# IO.net
KiCad netlist of a schematic drawn in Altium Designer
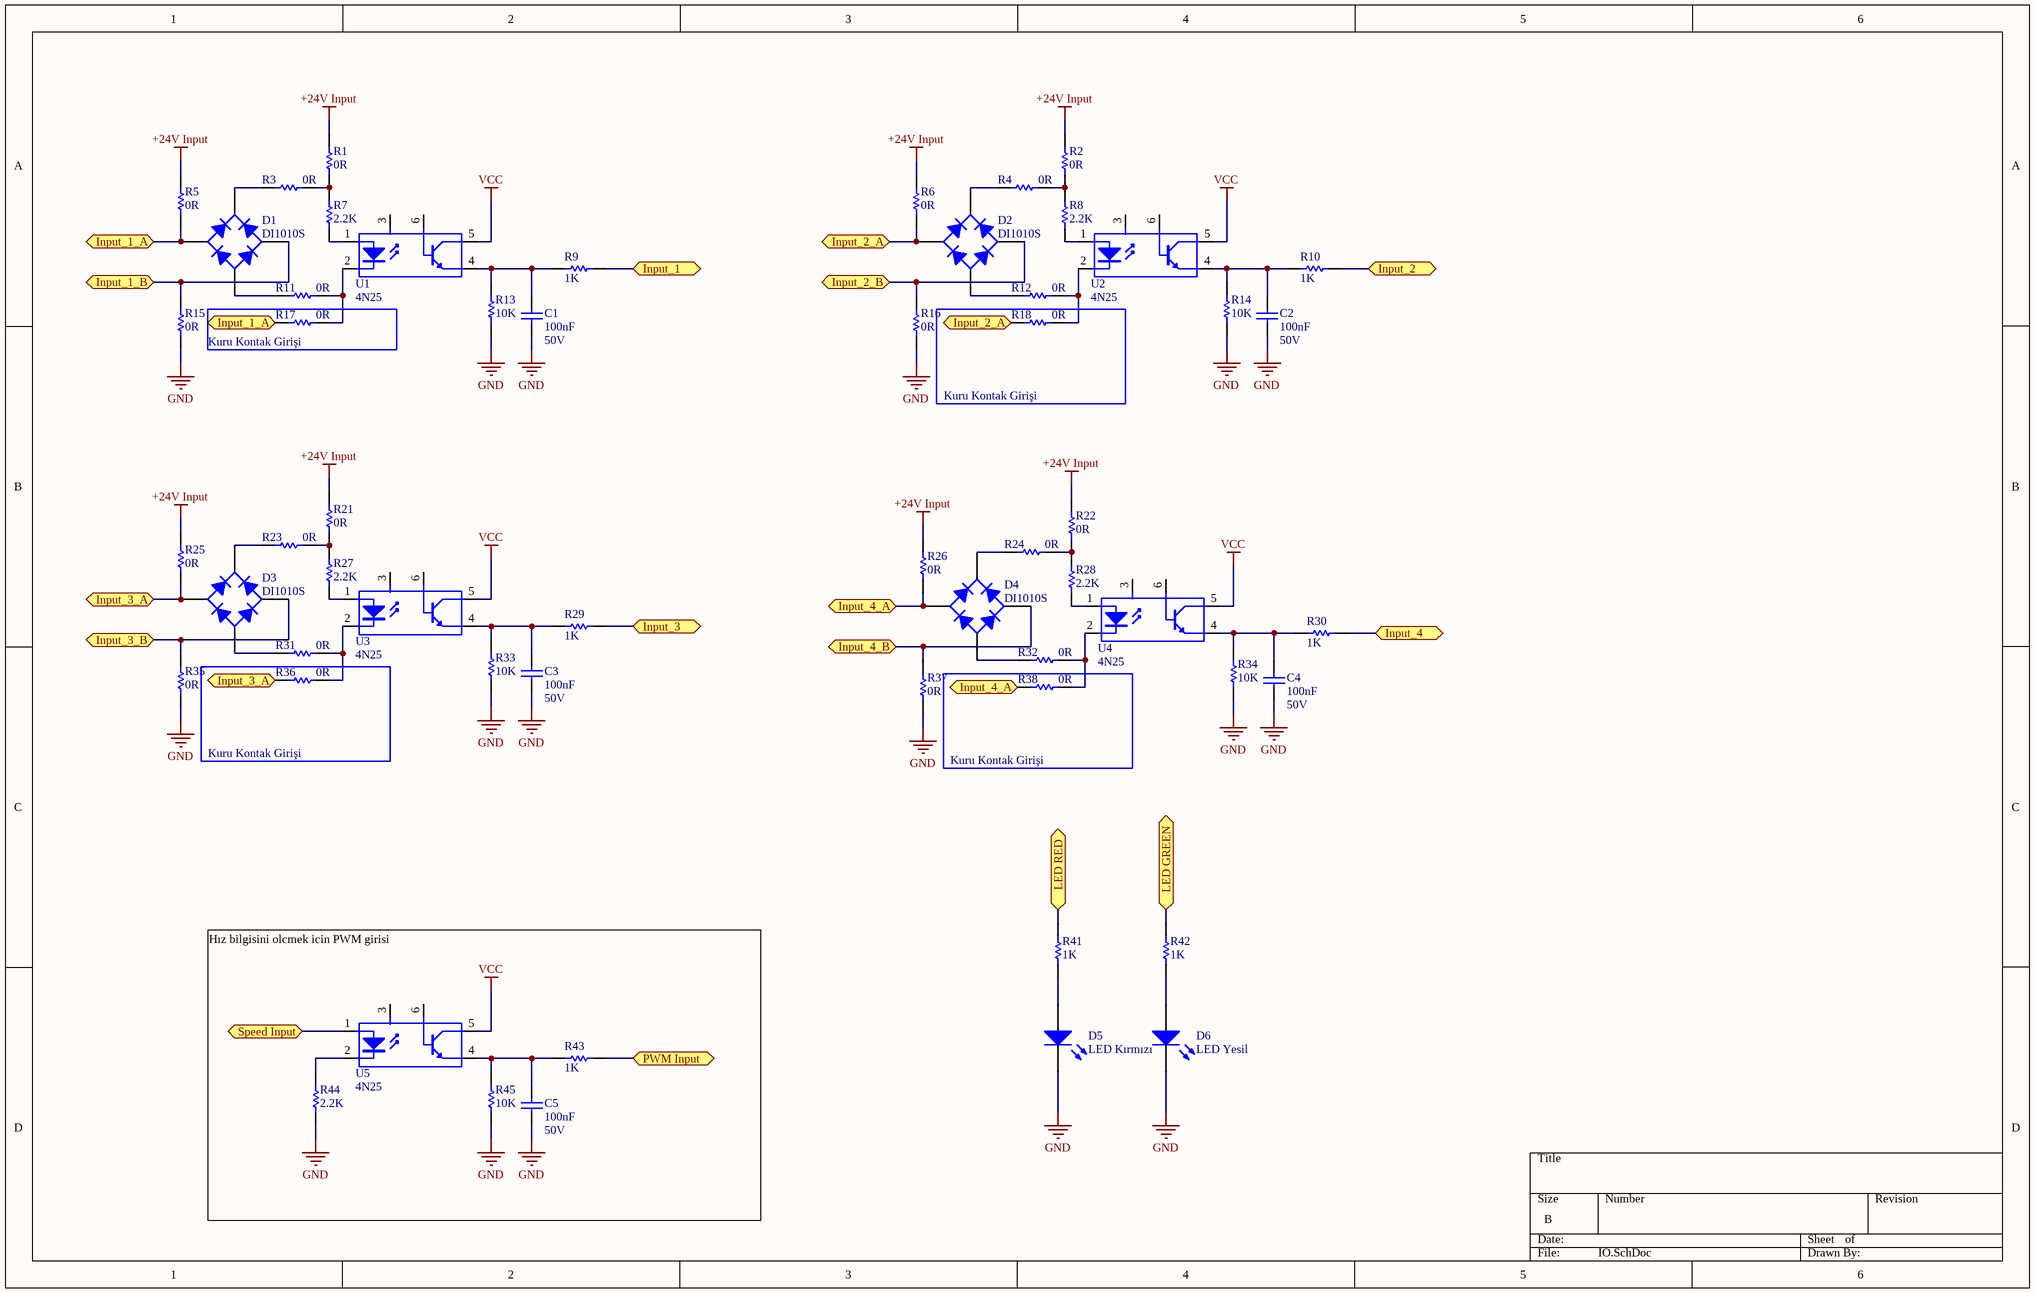
[diagram p0: IO.SchDoc]

(export (version "E")
  (design (tool "Eeschema 10.0.6"))
  (components
    (comp (ref "C1")
      (value "100nF")
      (footprint "3-0603_L")
      (description "Capacitor")
      (fields
        (field (name "VOLTAGE") "50V")
        (field (name "Comment") "Cap")
        (field (name "PUBLISHER") "Altium Limited")
      )
      (libsource (lib "Erdem_05112012") (part "Cap"))
    )
    (comp (ref "C2")
      (value "100nF")
      (footprint "3-0603_L")
      (description "Capacitor")
      (fields
        (field (name "VOLTAGE") "50V")
        (field (name "Comment") "Cap")
        (field (name "PUBLISHER") "Altium Limited")
      )
      (libsource (lib "Erdem_05112012") (part "Cap"))
    )
    (comp (ref "C3")
      (value "100nF")
      (footprint "3-0603_L")
      (description "Capacitor")
      (fields
        (field (name "VOLTAGE") "50V")
        (field (name "Comment") "Cap")
        (field (name "PUBLISHER") "Altium Limited")
      )
      (libsource (lib "Erdem_05112012") (part "Cap"))
    )
    (comp (ref "C4")
      (value "100nF")
      (footprint "3-0603_L")
      (description "Capacitor")
      (fields
        (field (name "VOLTAGE") "50V")
        (field (name "Comment") "Cap")
        (field (name "PUBLISHER") "Altium Limited")
      )
      (libsource (lib "Erdem_05112012") (part "Cap"))
    )
    (comp (ref "C5")
      (value "100nF")
      (footprint "3-0603_L")
      (description "Capacitor")
      (fields
        (field (name "VOLTAGE") "50V")
        (field (name "Comment") "Cap")
        (field (name "PUBLISHER") "Altium Limited")
      )
      (libsource (lib "Erdem_05112012") (part "Cap"))
    )
    (comp (ref "D1")
      (value "DI1010S")
      (footprint "DF-S")
      (description "Full Wave Diode Bridge")
      (fields (field (name "PUBLISHER") "Altium Limited"))
      (libsource (lib "Erdem_05112012") (part "DI1010S"))
    )
    (comp (ref "D2")
      (value "DI1010S")
      (footprint "DF-S")
      (description "Full Wave Diode Bridge")
      (fields (field (name "PUBLISHER") "Altium Limited"))
      (libsource (lib "Erdem_05112012") (part "DI1010S"))
    )
    (comp (ref "D3")
      (value "DI1010S")
      (footprint "DF-S")
      (description "Full Wave Diode Bridge")
      (fields (field (name "PUBLISHER") "Altium Limited"))
      (libsource (lib "Erdem_05112012") (part "DI1010S"))
    )
    (comp (ref "D4")
      (value "DI1010S")
      (footprint "DF-S")
      (description "Full Wave Diode Bridge")
      (fields (field (name "PUBLISHER") "Altium Limited"))
      (libsource (lib "Erdem_05112012") (part "DI1010S"))
    )
    (comp (ref "D5")
      (value "LED Kırmızı")
      (footprint "6-0805 - LED")
      (description "Typical INFRARED GaAs LED")
      (fields (field (name "PUBLISHER") "Altium Limited"))
      (libsource (lib "Erdem_05112012") (part "LED"))
    )
    (comp (ref "D6")
      (value "LED Yesil")
      (footprint "6-0805 - LED")
      (description "Typical INFRARED GaAs LED")
      (fields (field (name "PUBLISHER") "Altium Limited"))
      (libsource (lib "Erdem_05112012") (part "LED"))
    )
    (comp (ref "R1")
      (value "0R")
      (footprint "6-0805_M")
      (description "Resistor")
      (fields (field (name "Comment") "Res1") (field (name "PUBLISHER") "Altium Limited"))
      (libsource (lib "Erdem_05112012") (part "Res1"))
    )
    (comp (ref "R2")
      (value "0R")
      (footprint "6-0805_M")
      (description "Resistor")
      (fields (field (name "Comment") "Res1") (field (name "PUBLISHER") "Altium Limited"))
      (libsource (lib "Erdem_05112012") (part "Res1"))
    )
    (comp (ref "R3")
      (value "0R")
      (footprint "6-0805_M")
      (description "Resistor")
      (fields (field (name "Comment") "Res1") (field (name "PUBLISHER") "Altium Limited"))
      (libsource (lib "Erdem_05112012") (part "Res1"))
    )
    (comp (ref "R4")
      (value "0R")
      (footprint "6-0805_M")
      (description "Resistor")
      (fields (field (name "Comment") "Res1") (field (name "PUBLISHER") "Altium Limited"))
      (libsource (lib "Erdem_05112012") (part "Res1"))
    )
    (comp (ref "R5")
      (value "0R")
      (footprint "6-0805_M")
      (description "Resistor")
      (fields (field (name "Comment") "Res1") (field (name "PUBLISHER") "Altium Limited"))
      (libsource (lib "Erdem_05112012") (part "Res1"))
    )
    (comp (ref "R6")
      (value "0R")
      (footprint "6-0805_M")
      (description "Resistor")
      (fields (field (name "Comment") "Res1") (field (name "PUBLISHER") "Altium Limited"))
      (libsource (lib "Erdem_05112012") (part "Res1"))
    )
    (comp (ref "R7")
      (value "2.2K")
      (footprint "6-0805_M")
      (description "Resistor")
      (fields (field (name "Comment") "Res1") (field (name "PUBLISHER") "Altium Limited"))
      (libsource (lib "Erdem_05112012") (part "Res1"))
    )
    (comp (ref "R8")
      (value "2.2K")
      (footprint "6-0805_M")
      (description "Resistor")
      (fields (field (name "Comment") "Res1") (field (name "PUBLISHER") "Altium Limited"))
      (libsource (lib "Erdem_05112012") (part "Res1"))
    )
    (comp (ref "R9")
      (value "1K")
      (footprint "3-0603_L")
      (description "Resistor")
      (fields (field (name "Comment") "Res1") (field (name "PUBLISHER") "Altium Limited"))
      (libsource (lib "Erdem_05112012") (part "Res1"))
    )
    (comp (ref "R10")
      (value "1K")
      (footprint "3-0603_L")
      (description "Resistor")
      (fields (field (name "Comment") "Res1") (field (name "PUBLISHER") "Altium Limited"))
      (libsource (lib "Erdem_05112012") (part "Res1"))
    )
    (comp (ref "R11")
      (value "0R")
      (footprint "6-0805_M")
      (description "Resistor")
      (fields (field (name "Comment") "Res1") (field (name "PUBLISHER") "Altium Limited"))
      (libsource (lib "Erdem_05112012") (part "Res1"))
    )
    (comp (ref "R12")
      (value "0R")
      (footprint "6-0805_M")
      (description "Resistor")
      (fields (field (name "Comment") "Res1") (field (name "PUBLISHER") "Altium Limited"))
      (libsource (lib "Erdem_05112012") (part "Res1"))
    )
    (comp (ref "R13")
      (value "10K")
      (footprint "3-0603_L")
      (description "Resistor")
      (fields (field (name "Comment") "Res1") (field (name "PUBLISHER") "Altium Limited"))
      (libsource (lib "Erdem_05112012") (part "Res1"))
    )
    (comp (ref "R14")
      (value "10K")
      (footprint "3-0603_L")
      (description "Resistor")
      (fields (field (name "Comment") "Res1") (field (name "PUBLISHER") "Altium Limited"))
      (libsource (lib "Erdem_05112012") (part "Res1"))
    )
    (comp (ref "R15")
      (value "0R")
      (footprint "6-0805_M")
      (description "Resistor")
      (fields (field (name "Comment") "Res1") (field (name "PUBLISHER") "Altium Limited"))
      (libsource (lib "Erdem_05112012") (part "Res1"))
    )
    (comp (ref "R16")
      (value "0R")
      (footprint "6-0805_M")
      (description "Resistor")
      (fields (field (name "Comment") "Res1") (field (name "PUBLISHER") "Altium Limited"))
      (libsource (lib "Erdem_05112012") (part "Res1"))
    )
    (comp (ref "R17")
      (value "0R")
      (footprint "6-0805_M")
      (description "Resistor")
      (fields (field (name "Comment") "Res1") (field (name "PUBLISHER") "Altium Limited"))
      (libsource (lib "Erdem_05112012") (part "Res1"))
    )
    (comp (ref "R18")
      (value "0R")
      (footprint "6-0805_M")
      (description "Resistor")
      (fields (field (name "Comment") "Res1") (field (name "PUBLISHER") "Altium Limited"))
      (libsource (lib "Erdem_05112012") (part "Res1"))
    )
    (comp (ref "R21")
      (value "0R")
      (footprint "6-0805_M")
      (description "Resistor")
      (fields (field (name "Comment") "Res1") (field (name "PUBLISHER") "Altium Limited"))
      (libsource (lib "Erdem_05112012") (part "Res1"))
    )
    (comp (ref "R22")
      (value "0R")
      (footprint "6-0805_M")
      (description "Resistor")
      (fields (field (name "Comment") "Res1") (field (name "PUBLISHER") "Altium Limited"))
      (libsource (lib "Erdem_05112012") (part "Res1"))
    )
    (comp (ref "R23")
      (value "0R")
      (footprint "6-0805_M")
      (description "Resistor")
      (fields (field (name "Comment") "Res1") (field (name "PUBLISHER") "Altium Limited"))
      (libsource (lib "Erdem_05112012") (part "Res1"))
    )
    (comp (ref "R24")
      (value "0R")
      (footprint "6-0805_M")
      (description "Resistor")
      (fields (field (name "Comment") "Res1") (field (name "PUBLISHER") "Altium Limited"))
      (libsource (lib "Erdem_05112012") (part "Res1"))
    )
    (comp (ref "R25")
      (value "0R")
      (footprint "6-0805_M")
      (description "Resistor")
      (fields (field (name "Comment") "Res1") (field (name "PUBLISHER") "Altium Limited"))
      (libsource (lib "Erdem_05112012") (part "Res1"))
    )
    (comp (ref "R26")
      (value "0R")
      (footprint "6-0805_M")
      (description "Resistor")
      (fields (field (name "Comment") "Res1") (field (name "PUBLISHER") "Altium Limited"))
      (libsource (lib "Erdem_05112012") (part "Res1"))
    )
    (comp (ref "R27")
      (value "2.2K")
      (footprint "6-0805_M")
      (description "Resistor")
      (fields (field (name "Comment") "Res1") (field (name "PUBLISHER") "Altium Limited"))
      (libsource (lib "Erdem_05112012") (part "Res1"))
    )
    (comp (ref "R28")
      (value "2.2K")
      (footprint "6-0805_M")
      (description "Resistor")
      (fields (field (name "Comment") "Res1") (field (name "PUBLISHER") "Altium Limited"))
      (libsource (lib "Erdem_05112012") (part "Res1"))
    )
    (comp (ref "R29")
      (value "1K")
      (footprint "3-0603_L")
      (description "Resistor")
      (fields (field (name "Comment") "Res1") (field (name "PUBLISHER") "Altium Limited"))
      (libsource (lib "Erdem_05112012") (part "Res1"))
    )
    (comp (ref "R30")
      (value "1K")
      (footprint "3-0603_L")
      (description "Resistor")
      (fields (field (name "Comment") "Res1") (field (name "PUBLISHER") "Altium Limited"))
      (libsource (lib "Erdem_05112012") (part "Res1"))
    )
    (comp (ref "R31")
      (value "0R")
      (footprint "6-0805_M")
      (description "Resistor")
      (fields (field (name "Comment") "Res1") (field (name "PUBLISHER") "Altium Limited"))
      (libsource (lib "Erdem_05112012") (part "Res1"))
    )
    (comp (ref "R32")
      (value "0R")
      (footprint "6-0805_M")
      (description "Resistor")
      (fields (field (name "Comment") "Res1") (field (name "PUBLISHER") "Altium Limited"))
      (libsource (lib "Erdem_05112012") (part "Res1"))
    )
    (comp (ref "R33")
      (value "10K")
      (footprint "3-0603_L")
      (description "Resistor")
      (fields (field (name "Comment") "Res1") (field (name "PUBLISHER") "Altium Limited"))
      (libsource (lib "Erdem_05112012") (part "Res1"))
    )
    (comp (ref "R34")
      (value "10K")
      (footprint "3-0603_L")
      (description "Resistor")
      (fields (field (name "Comment") "Res1") (field (name "PUBLISHER") "Altium Limited"))
      (libsource (lib "Erdem_05112012") (part "Res1"))
    )
    (comp (ref "R35")
      (value "0R")
      (footprint "6-0805_M")
      (description "Resistor")
      (fields (field (name "Comment") "Res1") (field (name "PUBLISHER") "Altium Limited"))
      (libsource (lib "Erdem_05112012") (part "Res1"))
    )
    (comp (ref "R36")
      (value "0R")
      (footprint "6-0805_M")
      (description "Resistor")
      (fields (field (name "Comment") "Res1") (field (name "PUBLISHER") "Altium Limited"))
      (libsource (lib "Erdem_05112012") (part "Res1"))
    )
    (comp (ref "R37")
      (value "0R")
      (footprint "6-0805_M")
      (description "Resistor")
      (fields (field (name "Comment") "Res1") (field (name "PUBLISHER") "Altium Limited"))
      (libsource (lib "Erdem_05112012") (part "Res1"))
    )
    (comp (ref "R38")
      (value "0R")
      (footprint "6-0805_M")
      (description "Resistor")
      (fields (field (name "Comment") "Res1") (field (name "PUBLISHER") "Altium Limited"))
      (libsource (lib "Erdem_05112012") (part "Res1"))
    )
    (comp (ref "R41")
      (value "1K")
      (footprint "3-0603_L")
      (description "Resistor")
      (fields (field (name "Comment") "Res1") (field (name "PUBLISHER") "Altium Limited"))
      (libsource (lib "Erdem_05112012") (part "Res1"))
    )
    (comp (ref "R42")
      (value "1K")
      (footprint "3-0603_L")
      (description "Resistor")
      (fields (field (name "Comment") "Res1") (field (name "PUBLISHER") "Altium Limited"))
      (libsource (lib "Erdem_05112012") (part "Res1"))
    )
    (comp (ref "R43")
      (value "1K")
      (footprint "3-0603_L")
      (description "Resistor")
      (fields (field (name "Comment") "Res1") (field (name "PUBLISHER") "Altium Limited"))
      (libsource (lib "Erdem_05112012") (part "Res1"))
    )
    (comp (ref "R44")
      (value "2.2K")
      (footprint "6-0805_M")
      (description "Resistor")
      (fields (field (name "Comment") "Res1") (field (name "PUBLISHER") "Altium Limited"))
      (libsource (lib "Erdem_05112012") (part "Res1"))
    )
    (comp (ref "R45")
      (value "10K")
      (footprint "3-0603_L")
      (description "Resistor")
      (fields (field (name "Comment") "Res1") (field (name "PUBLISHER") "Altium Limited"))
      (libsource (lib "Erdem_05112012") (part "Res1"))
    )
    (comp (ref "U1")
      (value "4N25")
      (footprint "DIP-6")
      (fields (field (name "PUBLISHER") "Altium Limited"))
      (libsource (lib "Erdem_05112012") (part "4N25"))
    )
    (comp (ref "U2")
      (value "4N25")
      (footprint "DIP-6")
      (fields (field (name "PUBLISHER") "Altium Limited"))
      (libsource (lib "Erdem_05112012") (part "4N25"))
    )
    (comp (ref "U3")
      (value "4N25")
      (footprint "DIP-6")
      (fields (field (name "PUBLISHER") "Altium Limited"))
      (libsource (lib "Erdem_05112012") (part "4N25"))
    )
    (comp (ref "U4")
      (value "4N25")
      (footprint "DIP-6")
      (fields (field (name "PUBLISHER") "Altium Limited"))
      (libsource (lib "Erdem_05112012") (part "4N25"))
    )
    (comp (ref "U5")
      (value "4N25")
      (footprint "DIP-6")
      (fields (field (name "PUBLISHER") "Altium Limited"))
      (libsource (lib "Erdem_05112012") (part "4N25"))
    )
  )
  (nets
    (net (code "1") (name "+24V Input") (class "Default")
      (node (ref "R1") (pin "2") (pinfunction "2_2") (pintype "passive"))
      (node (ref "R2") (pin "2") (pinfunction "2_2") (pintype "passive"))
      (node (ref "R21") (pin "2") (pinfunction "2_2") (pintype "passive"))
      (node (ref "R22") (pin "2") (pinfunction "2_2") (pintype "passive"))
      (node (ref "R25") (pin "2") (pinfunction "2_2") (pintype "passive"))
      (node (ref "R26") (pin "2") (pinfunction "2_2") (pintype "passive"))
      (node (ref "R5") (pin "2") (pinfunction "2_2") (pintype "passive"))
      (node (ref "R6") (pin "2") (pinfunction "2_2") (pintype "passive"))
    )
    (net (code "2") (name "/Input_1") (class "Default")
      (node (ref "R9") (pin "2") (pinfunction "2_2") (pintype "passive"))
    )
    (net (code "3") (name "/Input_1_A") (class "Default")
      (node (ref "D1") (pin "2") (pinfunction "C_2") (pintype "passive"))
      (node (ref "R17") (pin "2") (pinfunction "2_2") (pintype "passive"))
      (node (ref "R5") (pin "1") (pinfunction "1_1") (pintype "passive"))
    )
    (net (code "4") (name "/Input_1_B") (class "Default")
      (node (ref "D1") (pin "4") (pinfunction "C_4") (pintype "passive"))
      (node (ref "R15") (pin "2") (pinfunction "2_2") (pintype "passive"))
    )
    (net (code "5") (name "/Input_2") (class "Default")
      (node (ref "R10") (pin "2") (pinfunction "2_2") (pintype "passive"))
    )
    (net (code "6") (name "/Input_2_A") (class "Default")
      (node (ref "D2") (pin "2") (pinfunction "C_2") (pintype "passive"))
      (node (ref "R18") (pin "2") (pinfunction "2_2") (pintype "passive"))
      (node (ref "R6") (pin "1") (pinfunction "1_1") (pintype "passive"))
    )
    (net (code "7") (name "/Input_2_B") (class "Default")
      (node (ref "D2") (pin "4") (pinfunction "C_4") (pintype "passive"))
      (node (ref "R16") (pin "2") (pinfunction "2_2") (pintype "passive"))
    )
    (net (code "8") (name "/Input_3") (class "Default")
      (node (ref "R29") (pin "2") (pinfunction "2_2") (pintype "passive"))
    )
    (net (code "9") (name "/Input_3_A") (class "Default")
      (node (ref "D3") (pin "2") (pinfunction "C_2") (pintype "passive"))
      (node (ref "R25") (pin "1") (pinfunction "1_1") (pintype "passive"))
      (node (ref "R36") (pin "2") (pinfunction "2_2") (pintype "passive"))
    )
    (net (code "10") (name "/Input_3_B") (class "Default")
      (node (ref "D3") (pin "4") (pinfunction "C_4") (pintype "passive"))
      (node (ref "R35") (pin "2") (pinfunction "2_2") (pintype "passive"))
    )
    (net (code "11") (name "/Input_4") (class "Default")
      (node (ref "R30") (pin "2") (pinfunction "2_2") (pintype "passive"))
    )
    (net (code "12") (name "/Input_4_A") (class "Default")
      (node (ref "D4") (pin "2") (pinfunction "C_2") (pintype "passive"))
      (node (ref "R26") (pin "1") (pinfunction "1_1") (pintype "passive"))
      (node (ref "R38") (pin "2") (pinfunction "2_2") (pintype "passive"))
    )
    (net (code "13") (name "/Input_4_B") (class "Default")
      (node (ref "D4") (pin "4") (pinfunction "C_4") (pintype "passive"))
      (node (ref "R37") (pin "2") (pinfunction "2_2") (pintype "passive"))
    )
    (net (code "14") (name "/LED GREEN") (class "Default")
      (node (ref "R42") (pin "2") (pinfunction "2_2") (pintype "passive"))
    )
    (net (code "15") (name "/LED RED") (class "Default")
      (node (ref "R41") (pin "2") (pinfunction "2_2") (pintype "passive"))
    )
    (net (code "16") (name "/PWM Input") (class "Default")
      (node (ref "R43") (pin "2") (pinfunction "2_2") (pintype "passive"))
    )
    (net (code "17") (name "/Speed Input") (class "Default")
      (node (ref "U5") (pin "1") (pinfunction "A_1") (pintype "passive"))
    )
    (net (code "18") (name "GND") (class "Default")
      (node (ref "C1") (pin "2") (pinfunction "2_2") (pintype "passive"))
      (node (ref "C2") (pin "2") (pinfunction "2_2") (pintype "passive"))
      (node (ref "C3") (pin "2") (pinfunction "2_2") (pintype "passive"))
      (node (ref "C4") (pin "2") (pinfunction "2_2") (pintype "passive"))
      (node (ref "C5") (pin "2") (pinfunction "2_2") (pintype "passive"))
      (node (ref "D5") (pin "2") (pinfunction "K_2") (pintype "passive"))
      (node (ref "D6") (pin "2") (pinfunction "K_2") (pintype "passive"))
      (node (ref "R13") (pin "1") (pinfunction "1_1") (pintype "passive"))
      (node (ref "R14") (pin "1") (pinfunction "1_1") (pintype "passive"))
      (node (ref "R15") (pin "1") (pinfunction "1_1") (pintype "passive"))
      (node (ref "R16") (pin "1") (pinfunction "1_1") (pintype "passive"))
      (node (ref "R33") (pin "1") (pinfunction "1_1") (pintype "passive"))
      (node (ref "R34") (pin "1") (pinfunction "1_1") (pintype "passive"))
      (node (ref "R35") (pin "1") (pinfunction "1_1") (pintype "passive"))
      (node (ref "R37") (pin "1") (pinfunction "1_1") (pintype "passive"))
      (node (ref "R44") (pin "1") (pinfunction "1_1") (pintype "passive"))
      (node (ref "R45") (pin "1") (pinfunction "1_1") (pintype "passive"))
    )
    (net (code "19") (name "Net-(D1-A)") (class "Default")
      (node (ref "D1") (pin "1") (pinfunction "A_1") (pintype "passive"))
      (node (ref "R11") (pin "2") (pinfunction "2_2") (pintype "passive"))
    )
    (net (code "20") (name "Net-(D1-K)") (class "Default")
      (node (ref "D1") (pin "3") (pinfunction "K_3") (pintype "passive"))
      (node (ref "R3") (pin "2") (pinfunction "2_2") (pintype "passive"))
    )
    (net (code "21") (name "Net-(D2-A)") (class "Default")
      (node (ref "D2") (pin "1") (pinfunction "A_1") (pintype "passive"))
      (node (ref "R12") (pin "2") (pinfunction "2_2") (pintype "passive"))
    )
    (net (code "22") (name "Net-(D2-K)") (class "Default")
      (node (ref "D2") (pin "3") (pinfunction "K_3") (pintype "passive"))
      (node (ref "R4") (pin "2") (pinfunction "2_2") (pintype "passive"))
    )
    (net (code "23") (name "Net-(D3-A)") (class "Default")
      (node (ref "D3") (pin "1") (pinfunction "A_1") (pintype "passive"))
      (node (ref "R31") (pin "2") (pinfunction "2_2") (pintype "passive"))
    )
    (net (code "24") (name "Net-(D3-K)") (class "Default")
      (node (ref "D3") (pin "3") (pinfunction "K_3") (pintype "passive"))
      (node (ref "R23") (pin "2") (pinfunction "2_2") (pintype "passive"))
    )
    (net (code "25") (name "Net-(D4-A)") (class "Default")
      (node (ref "D4") (pin "1") (pinfunction "A_1") (pintype "passive"))
      (node (ref "R32") (pin "2") (pinfunction "2_2") (pintype "passive"))
    )
    (net (code "26") (name "Net-(D4-K)") (class "Default")
      (node (ref "D4") (pin "3") (pinfunction "K_3") (pintype "passive"))
      (node (ref "R24") (pin "2") (pinfunction "2_2") (pintype "passive"))
    )
    (net (code "27") (name "Net-(D5-A)") (class "Default")
      (node (ref "D5") (pin "1") (pinfunction "A_1") (pintype "passive"))
      (node (ref "R41") (pin "1") (pinfunction "1_1") (pintype "passive"))
    )
    (net (code "28") (name "Net-(D6-A)") (class "Default")
      (node (ref "D6") (pin "1") (pinfunction "A_1") (pintype "passive"))
      (node (ref "R42") (pin "1") (pinfunction "1_1") (pintype "passive"))
    )
    (net (code "29") (name "Net-(R1-Pad1)") (class "Default")
      (node (ref "R1") (pin "1") (pinfunction "1_1") (pintype "passive"))
      (node (ref "R3") (pin "1") (pinfunction "1_1") (pintype "passive"))
      (node (ref "R7") (pin "1") (pinfunction "1_1") (pintype "passive"))
    )
    (net (code "30") (name "Net-(R2-Pad1)") (class "Default")
      (node (ref "R2") (pin "1") (pinfunction "1_1") (pintype "passive"))
      (node (ref "R4") (pin "1") (pinfunction "1_1") (pintype "passive"))
      (node (ref "R8") (pin "1") (pinfunction "1_1") (pintype "passive"))
    )
    (net (code "31") (name "Net-(R21-Pad1)") (class "Default")
      (node (ref "R21") (pin "1") (pinfunction "1_1") (pintype "passive"))
      (node (ref "R23") (pin "1") (pinfunction "1_1") (pintype "passive"))
      (node (ref "R27") (pin "1") (pinfunction "1_1") (pintype "passive"))
    )
    (net (code "32") (name "Net-(R22-Pad1)") (class "Default")
      (node (ref "R22") (pin "1") (pinfunction "1_1") (pintype "passive"))
      (node (ref "R24") (pin "1") (pinfunction "1_1") (pintype "passive"))
      (node (ref "R28") (pin "1") (pinfunction "1_1") (pintype "passive"))
    )
    (net (code "33") (name "Net-(U1-A)") (class "Default")
      (node (ref "R7") (pin "2") (pinfunction "2_2") (pintype "passive"))
      (node (ref "U1") (pin "1") (pinfunction "A_1") (pintype "passive"))
    )
    (net (code "34") (name "Net-(U1-E)") (class "Default")
      (node (ref "C1") (pin "1") (pinfunction "1_1") (pintype "passive"))
      (node (ref "R13") (pin "2") (pinfunction "2_2") (pintype "passive"))
      (node (ref "R9") (pin "1") (pinfunction "1_1") (pintype "passive"))
      (node (ref "U1") (pin "4") (pinfunction "E_4") (pintype "passive"))
    )
    (net (code "35") (name "Net-(U1-K)") (class "Default")
      (node (ref "R11") (pin "1") (pinfunction "1_1") (pintype "passive"))
      (node (ref "R17") (pin "1") (pinfunction "1_1") (pintype "passive"))
      (node (ref "U1") (pin "2") (pinfunction "K_2") (pintype "passive"))
    )
    (net (code "36") (name "Net-(U2-A)") (class "Default")
      (node (ref "R8") (pin "2") (pinfunction "2_2") (pintype "passive"))
      (node (ref "U2") (pin "1") (pinfunction "A_1") (pintype "passive"))
    )
    (net (code "37") (name "Net-(U2-E)") (class "Default")
      (node (ref "C2") (pin "1") (pinfunction "1_1") (pintype "passive"))
      (node (ref "R10") (pin "1") (pinfunction "1_1") (pintype "passive"))
      (node (ref "R14") (pin "2") (pinfunction "2_2") (pintype "passive"))
      (node (ref "U2") (pin "4") (pinfunction "E_4") (pintype "passive"))
    )
    (net (code "38") (name "Net-(U2-K)") (class "Default")
      (node (ref "R12") (pin "1") (pinfunction "1_1") (pintype "passive"))
      (node (ref "R18") (pin "1") (pinfunction "1_1") (pintype "passive"))
      (node (ref "U2") (pin "2") (pinfunction "K_2") (pintype "passive"))
    )
    (net (code "39") (name "Net-(U3-A)") (class "Default")
      (node (ref "R27") (pin "2") (pinfunction "2_2") (pintype "passive"))
      (node (ref "U3") (pin "1") (pinfunction "A_1") (pintype "passive"))
    )
    (net (code "40") (name "Net-(U3-E)") (class "Default")
      (node (ref "C3") (pin "1") (pinfunction "1_1") (pintype "passive"))
      (node (ref "R29") (pin "1") (pinfunction "1_1") (pintype "passive"))
      (node (ref "R33") (pin "2") (pinfunction "2_2") (pintype "passive"))
      (node (ref "U3") (pin "4") (pinfunction "E_4") (pintype "passive"))
    )
    (net (code "41") (name "Net-(U3-K)") (class "Default")
      (node (ref "R31") (pin "1") (pinfunction "1_1") (pintype "passive"))
      (node (ref "R36") (pin "1") (pinfunction "1_1") (pintype "passive"))
      (node (ref "U3") (pin "2") (pinfunction "K_2") (pintype "passive"))
    )
    (net (code "42") (name "Net-(U4-A)") (class "Default")
      (node (ref "R28") (pin "2") (pinfunction "2_2") (pintype "passive"))
      (node (ref "U4") (pin "1") (pinfunction "A_1") (pintype "passive"))
    )
    (net (code "43") (name "Net-(U4-E)") (class "Default")
      (node (ref "C4") (pin "1") (pinfunction "1_1") (pintype "passive"))
      (node (ref "R30") (pin "1") (pinfunction "1_1") (pintype "passive"))
      (node (ref "R34") (pin "2") (pinfunction "2_2") (pintype "passive"))
      (node (ref "U4") (pin "4") (pinfunction "E_4") (pintype "passive"))
    )
    (net (code "44") (name "Net-(U4-K)") (class "Default")
      (node (ref "R32") (pin "1") (pinfunction "1_1") (pintype "passive"))
      (node (ref "R38") (pin "1") (pinfunction "1_1") (pintype "passive"))
      (node (ref "U4") (pin "2") (pinfunction "K_2") (pintype "passive"))
    )
    (net (code "45") (name "Net-(U5-E)") (class "Default")
      (node (ref "C5") (pin "1") (pinfunction "1_1") (pintype "passive"))
      (node (ref "R43") (pin "1") (pinfunction "1_1") (pintype "passive"))
      (node (ref "R45") (pin "2") (pinfunction "2_2") (pintype "passive"))
      (node (ref "U5") (pin "4") (pinfunction "E_4") (pintype "passive"))
    )
    (net (code "46") (name "Net-(U5-K)") (class "Default")
      (node (ref "R44") (pin "2") (pinfunction "2_2") (pintype "passive"))
      (node (ref "U5") (pin "2") (pinfunction "K_2") (pintype "passive"))
    )
    (net (code "47") (name "VCC") (class "Default")
      (node (ref "U1") (pin "5") (pinfunction "C_5") (pintype "passive"))
      (node (ref "U2") (pin "5") (pinfunction "C_5") (pintype "passive"))
      (node (ref "U3") (pin "5") (pinfunction "C_5") (pintype "passive"))
      (node (ref "U4") (pin "5") (pinfunction "C_5") (pintype "passive"))
      (node (ref "U5") (pin "5") (pinfunction "C_5") (pintype "passive"))
    )
    (net (code "48") (name "unconnected-(U1-B-Pad6)") (class "Default")
      (node (ref "U1") (pin "6") (pinfunction "B_6") (pintype "passive"))
    )
    (net (code "49") (name "unconnected-(U1-NC-Pad3)") (class "Default")
      (node (ref "U1") (pin "3") (pinfunction "NC_3") (pintype "passive"))
    )
    (net (code "50") (name "unconnected-(U2-B-Pad6)") (class "Default")
      (node (ref "U2") (pin "6") (pinfunction "B_6") (pintype "passive"))
    )
    (net (code "51") (name "unconnected-(U2-NC-Pad3)") (class "Default")
      (node (ref "U2") (pin "3") (pinfunction "NC_3") (pintype "passive"))
    )
    (net (code "52") (name "unconnected-(U3-B-Pad6)") (class "Default")
      (node (ref "U3") (pin "6") (pinfunction "B_6") (pintype "passive"))
    )
    (net (code "53") (name "unconnected-(U3-NC-Pad3)") (class "Default")
      (node (ref "U3") (pin "3") (pinfunction "NC_3") (pintype "passive"))
    )
    (net (code "54") (name "unconnected-(U4-B-Pad6)") (class "Default")
      (node (ref "U4") (pin "6") (pinfunction "B_6") (pintype "passive"))
    )
    (net (code "55") (name "unconnected-(U4-NC-Pad3)") (class "Default")
      (node (ref "U4") (pin "3") (pinfunction "NC_3") (pintype "passive"))
    )
    (net (code "56") (name "unconnected-(U5-B-Pad6)") (class "Default")
      (node (ref "U5") (pin "6") (pinfunction "B_6") (pintype "passive"))
    )
    (net (code "57") (name "unconnected-(U5-NC-Pad3)") (class "Default")
      (node (ref "U5") (pin "3") (pinfunction "NC_3") (pintype "passive"))
    )
  )
)
